# NE555.net
KiCad netlist of a schematic drawn in Altium Designer
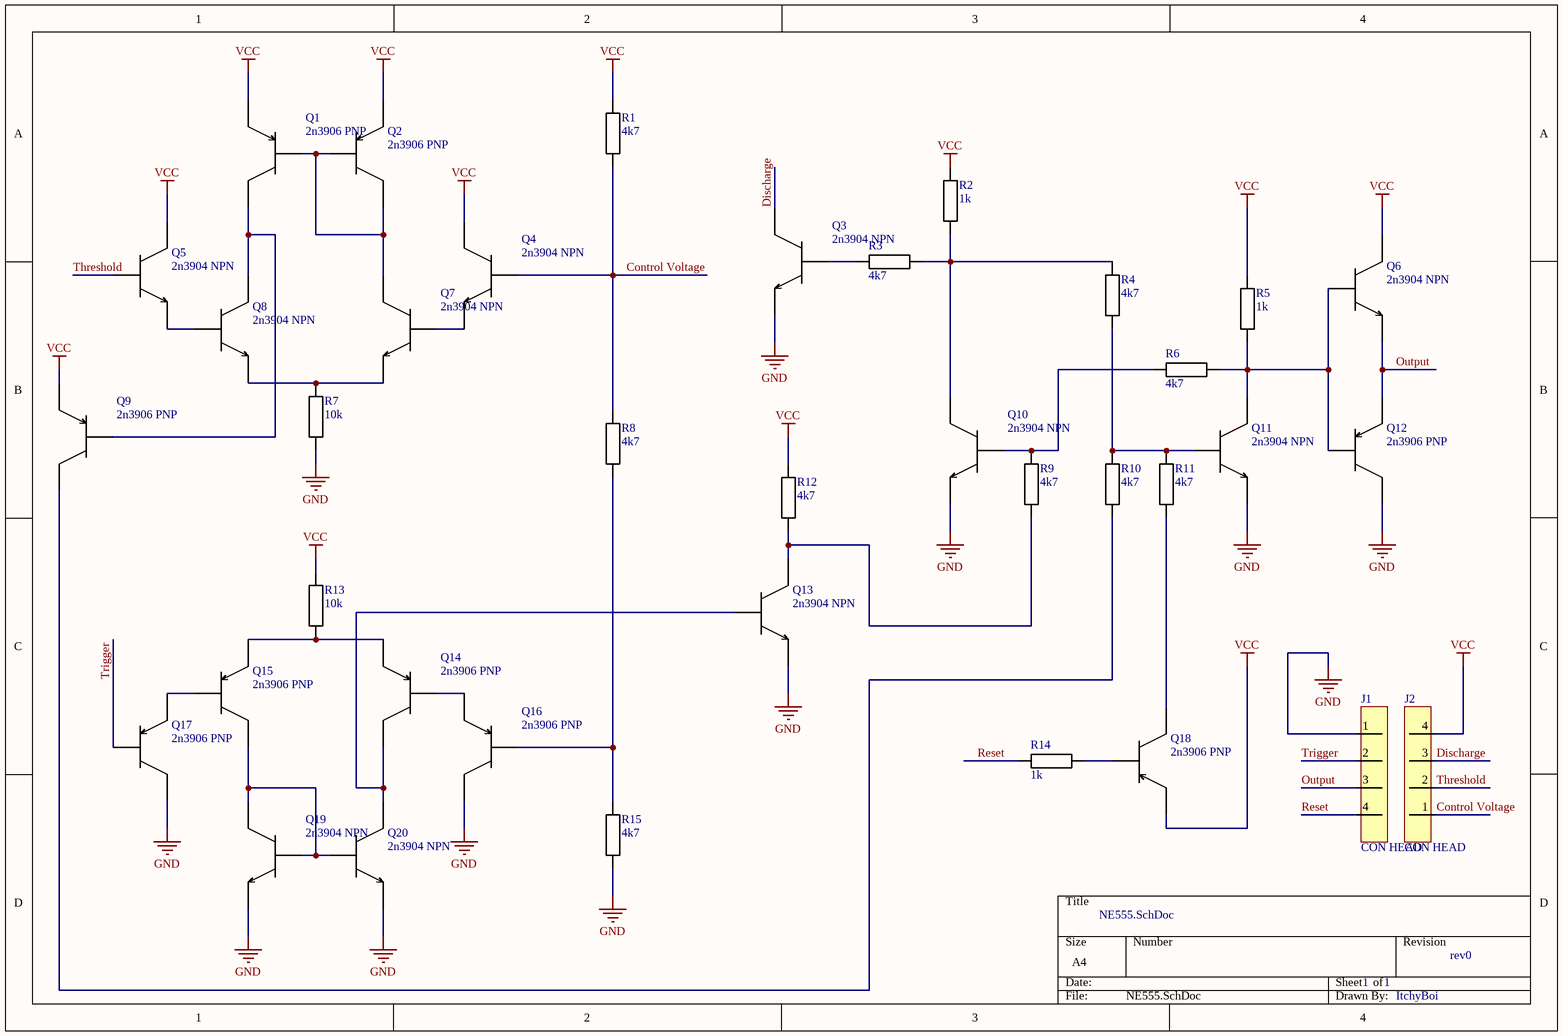
[diagram p0: NE555.SchDoc]

(export (version "E")
  (design (tool "Eeschema 10.0.6"))
  (components
    (comp (ref "J1")
      (value "CON HEAD")
      (footprint "SMT 4 HEADER 2.54")
      (description "CONN HEADER 4POS VERT 2.54MM SMD")
      (fields (field (name "MANUFACTURER") "Molex") (field (name "MANUFACTURER PART NUMBER") "0878980426"))
      (libsource (lib "") (part "0878980426_1"))
    )
    (comp (ref "J2")
      (value "CON HEAD")
      (footprint "SMT 4 HEADER 2.54")
      (description "CONN HEADER 4POS VERT 2.54MM SMD")
      (fields (field (name "MANUFACTURER") "Molex") (field (name "MANUFACTURER PART NUMBER") "0878980426"))
      (libsource (lib "Schlib1") (part "0878980426"))
    )
    (comp (ref "Q1")
      (value "2n3906 PNP")
      (footprint "SOT95P240X110-3N")
      (description "TRANS PNP 40V 0.2A SOT-23")
      (fields
        (field (name "MANUFACTURER") "ON Semiconductor / Fairchild")
        (field (name "MANUFACTURER PART NUMBER") "MMBT3906")
      )
      (libsource (lib "Schlib1") (part "MMBT3906"))
    )
    (comp (ref "Q2")
      (value "2n3906 PNP")
      (footprint "SOT95P240X110-3N")
      (description "TRANS PNP 40V 0.2A SOT-23")
      (fields
        (field (name "MANUFACTURER") "ON Semiconductor / Fairchild")
        (field (name "MANUFACTURER PART NUMBER") "MMBT3906")
      )
      (libsource (lib "Schlib1") (part "MMBT3906"))
    )
    (comp (ref "Q3")
      (value "2n3904 NPN")
      (footprint "SOT95P240X110-3N")
      (description "Trans Gp Bjt NPN 40V 0.2A 3-PIN SOT-23 T/r Trans Gp Bjt NPN 40V 0.2A 3-PIN SOT-23 T/r")
      (fields
        (field (name "MANUFACTURER") "ON Semiconductor / Fairchild")
        (field (name "MANUFACTURER PART NUMBER") "MMBT3904")
      )
      (libsource (lib "Schlib1") (part "MMBT3904"))
    )
    (comp (ref "Q4")
      (value "2n3904 NPN")
      (footprint "SOT95P240X110-3N")
      (description "Trans Gp Bjt NPN 40V 0.2A 3-PIN SOT-23 T/r Trans Gp Bjt NPN 40V 0.2A 3-PIN SOT-23 T/r")
      (fields
        (field (name "MANUFACTURER") "ON Semiconductor / Fairchild")
        (field (name "MANUFACTURER PART NUMBER") "MMBT3904")
      )
      (libsource (lib "Schlib1") (part "MMBT3904"))
    )
    (comp (ref "Q5")
      (value "2n3904 NPN")
      (footprint "SOT95P240X110-3N")
      (description "Trans Gp Bjt NPN 40V 0.2A 3-PIN SOT-23 T/r Trans Gp Bjt NPN 40V 0.2A 3-PIN SOT-23 T/r")
      (fields
        (field (name "MANUFACTURER") "ON Semiconductor / Fairchild")
        (field (name "MANUFACTURER PART NUMBER") "MMBT3904")
      )
      (libsource (lib "Schlib1") (part "MMBT3904"))
    )
    (comp (ref "Q6")
      (value "2n3904 NPN")
      (footprint "SOT95P240X110-3N")
      (description "Trans Gp Bjt NPN 40V 0.2A 3-PIN SOT-23 T/r Trans Gp Bjt NPN 40V 0.2A 3-PIN SOT-23 T/r")
      (fields
        (field (name "MANUFACTURER") "ON Semiconductor / Fairchild")
        (field (name "MANUFACTURER PART NUMBER") "MMBT3904")
      )
      (libsource (lib "Schlib1") (part "MMBT3904"))
    )
    (comp (ref "Q7")
      (value "2n3904 NPN")
      (footprint "SOT95P240X110-3N")
      (description "Trans Gp Bjt NPN 40V 0.2A 3-PIN SOT-23 T/r Trans Gp Bjt NPN 40V 0.2A 3-PIN SOT-23 T/r")
      (fields
        (field (name "MANUFACTURER") "ON Semiconductor / Fairchild")
        (field (name "MANUFACTURER PART NUMBER") "MMBT3904")
      )
      (libsource (lib "Schlib1") (part "MMBT3904"))
    )
    (comp (ref "Q8")
      (value "2n3904 NPN")
      (footprint "SOT95P240X110-3N")
      (description "Trans Gp Bjt NPN 40V 0.2A 3-PIN SOT-23 T/r Trans Gp Bjt NPN 40V 0.2A 3-PIN SOT-23 T/r")
      (fields
        (field (name "MANUFACTURER") "ON Semiconductor / Fairchild")
        (field (name "MANUFACTURER PART NUMBER") "MMBT3904")
      )
      (libsource (lib "Schlib1") (part "MMBT3904"))
    )
    (comp (ref "Q9")
      (value "2n3906 PNP")
      (footprint "SOT95P240X110-3N")
      (description "TRANS PNP 40V 0.2A SOT-23")
      (fields
        (field (name "MANUFACTURER") "ON Semiconductor / Fairchild")
        (field (name "MANUFACTURER PART NUMBER") "MMBT3906")
      )
      (libsource (lib "Schlib1") (part "MMBT3906"))
    )
    (comp (ref "Q10")
      (value "2n3904 NPN")
      (footprint "SOT95P240X110-3N")
      (description "Trans Gp Bjt NPN 40V 0.2A 3-PIN SOT-23 T/r Trans Gp Bjt NPN 40V 0.2A 3-PIN SOT-23 T/r")
      (fields
        (field (name "MANUFACTURER") "ON Semiconductor / Fairchild")
        (field (name "MANUFACTURER PART NUMBER") "MMBT3904")
      )
      (libsource (lib "Schlib1") (part "MMBT3904"))
    )
    (comp (ref "Q11")
      (value "2n3904 NPN")
      (footprint "SOT95P240X110-3N")
      (description "Trans Gp Bjt NPN 40V 0.2A 3-PIN SOT-23 T/r Trans Gp Bjt NPN 40V 0.2A 3-PIN SOT-23 T/r")
      (fields
        (field (name "MANUFACTURER") "ON Semiconductor / Fairchild")
        (field (name "MANUFACTURER PART NUMBER") "MMBT3904")
      )
      (libsource (lib "Schlib1") (part "MMBT3904"))
    )
    (comp (ref "Q12")
      (value "2n3906 PNP")
      (footprint "SOT95P240X110-3N")
      (description "TRANS PNP 40V 0.2A SOT-23")
      (fields
        (field (name "MANUFACTURER") "ON Semiconductor / Fairchild")
        (field (name "MANUFACTURER PART NUMBER") "MMBT3906")
      )
      (libsource (lib "Schlib1") (part "MMBT3906"))
    )
    (comp (ref "Q13")
      (value "2n3904 NPN")
      (footprint "SOT95P240X110-3N")
      (description "Trans Gp Bjt NPN 40V 0.2A 3-PIN SOT-23 T/r Trans Gp Bjt NPN 40V 0.2A 3-PIN SOT-23 T/r")
      (fields
        (field (name "MANUFACTURER") "ON Semiconductor / Fairchild")
        (field (name "MANUFACTURER PART NUMBER") "MMBT3904")
      )
      (libsource (lib "Schlib1") (part "MMBT3904"))
    )
    (comp (ref "Q14")
      (value "2n3906 PNP")
      (footprint "SOT95P240X110-3N")
      (description "TRANS PNP 40V 0.2A SOT-23")
      (fields
        (field (name "MANUFACTURER") "ON Semiconductor / Fairchild")
        (field (name "MANUFACTURER PART NUMBER") "MMBT3906")
      )
      (libsource (lib "Schlib1") (part "MMBT3906"))
    )
    (comp (ref "Q15")
      (value "2n3906 PNP")
      (footprint "SOT95P240X110-3N")
      (description "TRANS PNP 40V 0.2A SOT-23")
      (fields
        (field (name "MANUFACTURER") "ON Semiconductor / Fairchild")
        (field (name "MANUFACTURER PART NUMBER") "MMBT3906")
      )
      (libsource (lib "Schlib1") (part "MMBT3906"))
    )
    (comp (ref "Q16")
      (value "2n3906 PNP")
      (footprint "SOT95P240X110-3N")
      (description "TRANS PNP 40V 0.2A SOT-23")
      (fields
        (field (name "MANUFACTURER") "ON Semiconductor / Fairchild")
        (field (name "MANUFACTURER PART NUMBER") "MMBT3906")
      )
      (libsource (lib "Schlib1") (part "MMBT3906"))
    )
    (comp (ref "Q17")
      (value "2n3906 PNP")
      (footprint "SOT95P240X110-3N")
      (description "TRANS PNP 40V 0.2A SOT-23")
      (fields
        (field (name "MANUFACTURER") "ON Semiconductor / Fairchild")
        (field (name "MANUFACTURER PART NUMBER") "MMBT3906")
      )
      (libsource (lib "Schlib1") (part "MMBT3906"))
    )
    (comp (ref "Q18")
      (value "2n3906 PNP")
      (footprint "SOT95P240X110-3N")
      (description "TRANS PNP 40V 0.2A SOT-23")
      (fields
        (field (name "MANUFACTURER") "ON Semiconductor / Fairchild")
        (field (name "MANUFACTURER PART NUMBER") "MMBT3906")
      )
      (libsource (lib "Schlib1") (part "MMBT3906"))
    )
    (comp (ref "Q19")
      (value "2n3904 NPN")
      (footprint "SOT95P240X110-3N")
      (description "Trans Gp Bjt NPN 40V 0.2A 3-PIN SOT-23 T/r Trans Gp Bjt NPN 40V 0.2A 3-PIN SOT-23 T/r")
      (fields
        (field (name "MANUFACTURER") "ON Semiconductor / Fairchild")
        (field (name "MANUFACTURER PART NUMBER") "MMBT3904")
      )
      (libsource (lib "Schlib1") (part "MMBT3904"))
    )
    (comp (ref "Q20")
      (value "2n3904 NPN")
      (footprint "SOT95P240X110-3N")
      (description "Trans Gp Bjt NPN 40V 0.2A 3-PIN SOT-23 T/r Trans Gp Bjt NPN 40V 0.2A 3-PIN SOT-23 T/r")
      (fields
        (field (name "MANUFACTURER") "ON Semiconductor / Fairchild")
        (field (name "MANUFACTURER PART NUMBER") "MMBT3904")
      )
      (libsource (lib "Schlib1") (part "MMBT3904"))
    )
    (comp (ref "R1")
      (value "4k7")
      (footprint "R0805")
      (fields
        (field (name "MANUFACTURER") "Vishay")
        (field (name "MANUFACTURER PART NUMBER") "CRCW08054K70FKEA")
        (field (name "TOLERANCE") "1%")
      )
      (libsource (lib "Schlib1") (part "CRCW08054K70FKEA"))
    )
    (comp (ref "R2")
      (value "1k")
      (footprint "R0805")
      (description "Res Thick Film 0805 1K Ohm 1% 0.125W(1/8W) ±100ppm/C Pad SMD Automotive T/R")
      (fields
        (field (name "MANUFACTURER") "Vishay Dale")
        (field (name "MANUFACTURER PART NUMBER") "CRCW08051K00FKEA")
      )
      (libsource (lib "Schlib1") (part "CRCW08051K00FKEA"))
    )
    (comp (ref "R3")
      (value "4k7")
      (footprint "R0805")
      (fields
        (field (name "MANUFACTURER") "Vishay")
        (field (name "MANUFACTURER PART NUMBER") "CRCW08054K70FKEA")
        (field (name "TOLERANCE") "1%")
      )
      (libsource (lib "Schlib1") (part "CRCW08054K70FKEA"))
    )
    (comp (ref "R4")
      (value "4k7")
      (footprint "R0805")
      (fields
        (field (name "MANUFACTURER") "Vishay")
        (field (name "MANUFACTURER PART NUMBER") "CRCW08054K70FKEA")
        (field (name "TOLERANCE") "1%")
      )
      (libsource (lib "Schlib1") (part "CRCW08054K70FKEA"))
    )
    (comp (ref "R5")
      (value "1k")
      (footprint "R0805")
      (description "Res Thick Film 0805 1K Ohm 1% 0.125W(1/8W) ±100ppm/C Pad SMD Automotive T/R")
      (fields
        (field (name "MANUFACTURER") "Vishay Dale")
        (field (name "MANUFACTURER PART NUMBER") "CRCW08051K00FKEA")
      )
      (libsource (lib "Schlib1") (part "CRCW08051K00FKEA"))
    )
    (comp (ref "R6")
      (value "4k7")
      (footprint "R0805")
      (fields
        (field (name "MANUFACTURER") "Vishay")
        (field (name "MANUFACTURER PART NUMBER") "CRCW08054K70FKEA")
        (field (name "TOLERANCE") "1%")
      )
      (libsource (lib "Schlib1") (part "CRCW08054K70FKEA"))
    )
    (comp (ref "R7")
      (value "10k")
      (footprint "R0805")
      (fields
        (field (name "MANUFACTURER") "Vishay")
        (field (name "MANUFACTURER PART NUMBER") "CRCW080510K0FKEA")
        (field (name "TOLERANCE") "1%")
      )
      (libsource (lib "Schlib1") (part "CRCW080510K0FKEA"))
    )
    (comp (ref "R8")
      (value "4k7")
      (footprint "R0805")
      (fields
        (field (name "MANUFACTURER") "Vishay")
        (field (name "MANUFACTURER PART NUMBER") "CRCW08054K70FKEA")
        (field (name "TOLERANCE") "1%")
      )
      (libsource (lib "Schlib1") (part "CRCW08054K70FKEA"))
    )
    (comp (ref "R9")
      (value "4k7")
      (footprint "R0805")
      (fields
        (field (name "MANUFACTURER") "Vishay")
        (field (name "MANUFACTURER PART NUMBER") "CRCW08054K70FKEA")
        (field (name "TOLERANCE") "1%")
      )
      (libsource (lib "Schlib1") (part "CRCW08054K70FKEA"))
    )
    (comp (ref "R10")
      (value "4k7")
      (footprint "R0805")
      (fields
        (field (name "MANUFACTURER") "Vishay")
        (field (name "MANUFACTURER PART NUMBER") "CRCW08054K70FKEA")
        (field (name "TOLERANCE") "1%")
      )
      (libsource (lib "Schlib1") (part "CRCW08054K70FKEA"))
    )
    (comp (ref "R11")
      (value "4k7")
      (footprint "R0805")
      (fields
        (field (name "MANUFACTURER") "Vishay")
        (field (name "MANUFACTURER PART NUMBER") "CRCW08054K70FKEA")
        (field (name "TOLERANCE") "1%")
      )
      (libsource (lib "Schlib1") (part "CRCW08054K70FKEA"))
    )
    (comp (ref "R12")
      (value "4k7")
      (footprint "R0805")
      (fields
        (field (name "MANUFACTURER") "Vishay")
        (field (name "MANUFACTURER PART NUMBER") "CRCW08054K70FKEA")
        (field (name "TOLERANCE") "1%")
      )
      (libsource (lib "Schlib1") (part "CRCW08054K70FKEA"))
    )
    (comp (ref "R13")
      (value "10k")
      (footprint "R0805")
      (fields
        (field (name "MANUFACTURER") "Vishay")
        (field (name "MANUFACTURER PART NUMBER") "CRCW080510K0FKEA")
        (field (name "TOLERANCE") "1%")
      )
      (libsource (lib "Schlib1") (part "CRCW080510K0FKEA"))
    )
    (comp (ref "R14")
      (value "1k")
      (footprint "R0805")
      (description "Res Thick Film 0805 1K Ohm 1% 0.125W(1/8W) ±100ppm/C Pad SMD Automotive T/R")
      (fields
        (field (name "MANUFACTURER") "Vishay Dale")
        (field (name "MANUFACTURER PART NUMBER") "CRCW08051K00FKEA")
      )
      (libsource (lib "Schlib1") (part "CRCW08051K00FKEA"))
    )
    (comp (ref "R15")
      (value "4k7")
      (footprint "R0805")
      (fields
        (field (name "MANUFACTURER") "Vishay")
        (field (name "MANUFACTURER PART NUMBER") "CRCW08054K70FKEA")
        (field (name "TOLERANCE") "1%")
      )
      (libsource (lib "Schlib1") (part "CRCW08054K70FKEA"))
    )
  )
  (nets
    (net (code "1") (name "/Control Voltage") (class "Default")
      (node (ref "J2") (pin "1") (pinfunction "1_1") (pintype "passive"))
      (node (ref "Q4") (pin "1") (pinfunction "B_1") (pintype "passive"))
      (node (ref "R1") (pin "2") (pinfunction "2_2") (pintype "passive"))
      (node (ref "R8") (pin "1") (pinfunction "1_1") (pintype "passive"))
    )
    (net (code "2") (name "/Discharge") (class "Default")
      (node (ref "J2") (pin "3") (pinfunction "3_3") (pintype "passive"))
      (node (ref "Q3") (pin "3") (pinfunction "C_3") (pintype "open_collector"))
    )
    (net (code "3") (name "/Output") (class "Default")
      (node (ref "J1") (pin "3") (pinfunction "3_3") (pintype "passive"))
      (node (ref "Q12") (pin "2") (pinfunction "E_2") (pintype "open_emitter"))
      (node (ref "Q6") (pin "2") (pinfunction "E_2") (pintype "open_emitter"))
    )
    (net (code "4") (name "/Reset") (class "Default")
      (node (ref "J1") (pin "4") (pinfunction "4_4") (pintype "passive"))
      (node (ref "R14") (pin "2") (pinfunction "2_2") (pintype "passive"))
    )
    (net (code "5") (name "/Threshold") (class "Default")
      (node (ref "J2") (pin "2") (pinfunction "2_2") (pintype "passive"))
      (node (ref "Q5") (pin "1") (pinfunction "B_1") (pintype "passive"))
    )
    (net (code "6") (name "/Trigger") (class "Default")
      (node (ref "J1") (pin "2") (pinfunction "2_2") (pintype "passive"))
      (node (ref "Q17") (pin "1") (pinfunction "B_1") (pintype "passive"))
    )
    (net (code "7") (name "GND") (class "Default")
      (node (ref "J1") (pin "1") (pinfunction "1_1") (pintype "passive"))
      (node (ref "Q10") (pin "2") (pinfunction "E_2") (pintype "open_emitter"))
      (node (ref "Q11") (pin "2") (pinfunction "E_2") (pintype "open_emitter"))
      (node (ref "Q12") (pin "3") (pinfunction "C_3") (pintype "open_collector"))
      (node (ref "Q13") (pin "2") (pinfunction "E_2") (pintype "open_emitter"))
      (node (ref "Q16") (pin "3") (pinfunction "C_3") (pintype "open_collector"))
      (node (ref "Q17") (pin "3") (pinfunction "C_3") (pintype "open_collector"))
      (node (ref "Q19") (pin "2") (pinfunction "E_2") (pintype "open_emitter"))
      (node (ref "Q20") (pin "2") (pinfunction "E_2") (pintype "open_emitter"))
      (node (ref "Q3") (pin "2") (pinfunction "E_2") (pintype "open_emitter"))
      (node (ref "R15") (pin "2") (pinfunction "2_2") (pintype "passive"))
      (node (ref "R7") (pin "1") (pinfunction "1_1") (pintype "passive"))
    )
    (net (code "8") (name "Net-(Q1-B)") (class "Default")
      (node (ref "Q1") (pin "1") (pinfunction "B_1") (pintype "passive"))
      (node (ref "Q2") (pin "1") (pinfunction "B_1") (pintype "passive"))
      (node (ref "Q2") (pin "3") (pinfunction "C_3") (pintype "open_collector"))
      (node (ref "Q7") (pin "3") (pinfunction "C_3") (pintype "open_collector"))
    )
    (net (code "9") (name "Net-(Q1-C)") (class "Default")
      (node (ref "Q1") (pin "3") (pinfunction "C_3") (pintype "open_collector"))
      (node (ref "Q8") (pin "3") (pinfunction "C_3") (pintype "open_collector"))
      (node (ref "Q9") (pin "1") (pinfunction "B_1") (pintype "passive"))
    )
    (net (code "10") (name "Net-(Q3-B)") (class "Default")
      (node (ref "Q3") (pin "1") (pinfunction "B_1") (pintype "passive"))
      (node (ref "R3") (pin "2") (pinfunction "2_2") (pintype "passive"))
    )
    (net (code "11") (name "Net-(Q4-E)") (class "Default")
      (node (ref "Q4") (pin "2") (pinfunction "E_2") (pintype "open_emitter"))
      (node (ref "Q7") (pin "1") (pinfunction "B_1") (pintype "passive"))
    )
    (net (code "12") (name "Net-(Q5-E)") (class "Default")
      (node (ref "Q5") (pin "2") (pinfunction "E_2") (pintype "open_emitter"))
      (node (ref "Q8") (pin "1") (pinfunction "B_1") (pintype "passive"))
    )
    (net (code "13") (name "Net-(Q7-E)") (class "Default")
      (node (ref "Q7") (pin "2") (pinfunction "E_2") (pintype "open_emitter"))
      (node (ref "Q8") (pin "2") (pinfunction "E_2") (pintype "open_emitter"))
      (node (ref "R7") (pin "2") (pinfunction "2_2") (pintype "passive"))
    )
    (net (code "14") (name "Net-(Q9-C)") (class "Default")
      (node (ref "Q9") (pin "3") (pinfunction "C_3") (pintype "open_collector"))
      (node (ref "R10") (pin "1") (pinfunction "1_1") (pintype "passive"))
    )
    (net (code "15") (name "Net-(Q10-B)") (class "Default")
      (node (ref "Q10") (pin "1") (pinfunction "B_1") (pintype "passive"))
      (node (ref "R6") (pin "1") (pinfunction "1_1") (pintype "passive"))
      (node (ref "R9") (pin "2") (pinfunction "2_2") (pintype "passive"))
    )
    (net (code "16") (name "Net-(Q10-C)") (class "Default")
      (node (ref "Q10") (pin "3") (pinfunction "C_3") (pintype "open_collector"))
      (node (ref "R2") (pin "1") (pinfunction "1_1") (pintype "passive"))
      (node (ref "R3") (pin "1") (pinfunction "1_1") (pintype "passive"))
      (node (ref "R4") (pin "2") (pinfunction "2_2") (pintype "passive"))
    )
    (net (code "17") (name "Net-(Q11-B)") (class "Default")
      (node (ref "Q11") (pin "1") (pinfunction "B_1") (pintype "passive"))
      (node (ref "R10") (pin "2") (pinfunction "2_2") (pintype "passive"))
      (node (ref "R11") (pin "1") (pinfunction "1_1") (pintype "passive"))
      (node (ref "R4") (pin "1") (pinfunction "1_1") (pintype "passive"))
    )
    (net (code "18") (name "Net-(Q11-C)") (class "Default")
      (node (ref "Q11") (pin "3") (pinfunction "C_3") (pintype "open_collector"))
      (node (ref "Q12") (pin "1") (pinfunction "B_1") (pintype "passive"))
      (node (ref "Q6") (pin "1") (pinfunction "B_1") (pintype "passive"))
      (node (ref "R5") (pin "1") (pinfunction "1_1") (pintype "passive"))
      (node (ref "R6") (pin "2") (pinfunction "2_2") (pintype "passive"))
    )
    (net (code "19") (name "Net-(Q13-B)") (class "Default")
      (node (ref "Q13") (pin "1") (pinfunction "B_1") (pintype "passive"))
      (node (ref "Q14") (pin "3") (pinfunction "C_3") (pintype "open_collector"))
      (node (ref "Q20") (pin "3") (pinfunction "C_3") (pintype "open_collector"))
    )
    (net (code "20") (name "Net-(Q13-C)") (class "Default")
      (node (ref "Q13") (pin "3") (pinfunction "C_3") (pintype "open_collector"))
      (node (ref "R12") (pin "2") (pinfunction "2_2") (pintype "passive"))
      (node (ref "R9") (pin "1") (pinfunction "1_1") (pintype "passive"))
    )
    (net (code "21") (name "Net-(Q14-B)") (class "Default")
      (node (ref "Q14") (pin "1") (pinfunction "B_1") (pintype "passive"))
      (node (ref "Q16") (pin "2") (pinfunction "E_2") (pintype "open_emitter"))
    )
    (net (code "22") (name "Net-(Q14-E)") (class "Default")
      (node (ref "Q14") (pin "2") (pinfunction "E_2") (pintype "open_emitter"))
      (node (ref "Q15") (pin "2") (pinfunction "E_2") (pintype "open_emitter"))
      (node (ref "R13") (pin "1") (pinfunction "1_1") (pintype "passive"))
    )
    (net (code "23") (name "Net-(Q15-B)") (class "Default")
      (node (ref "Q15") (pin "1") (pinfunction "B_1") (pintype "passive"))
      (node (ref "Q17") (pin "2") (pinfunction "E_2") (pintype "open_emitter"))
    )
    (net (code "24") (name "Net-(Q15-C)") (class "Default")
      (node (ref "Q15") (pin "3") (pinfunction "C_3") (pintype "open_collector"))
      (node (ref "Q19") (pin "1") (pinfunction "B_1") (pintype "passive"))
      (node (ref "Q19") (pin "3") (pinfunction "C_3") (pintype "open_collector"))
      (node (ref "Q20") (pin "1") (pinfunction "B_1") (pintype "passive"))
    )
    (net (code "25") (name "Net-(Q16-B)") (class "Default")
      (node (ref "Q16") (pin "1") (pinfunction "B_1") (pintype "passive"))
      (node (ref "R15") (pin "1") (pinfunction "1_1") (pintype "passive"))
      (node (ref "R8") (pin "2") (pinfunction "2_2") (pintype "passive"))
    )
    (net (code "26") (name "Net-(Q18-B)") (class "Default")
      (node (ref "Q18") (pin "1") (pinfunction "B_1") (pintype "passive"))
      (node (ref "R14") (pin "1") (pinfunction "1_1") (pintype "passive"))
    )
    (net (code "27") (name "Net-(Q18-C)") (class "Default")
      (node (ref "Q18") (pin "3") (pinfunction "C_3") (pintype "open_collector"))
      (node (ref "R11") (pin "2") (pinfunction "2_2") (pintype "passive"))
    )
    (net (code "28") (name "VCC") (class "Default")
      (node (ref "J2") (pin "4") (pinfunction "4_4") (pintype "passive"))
      (node (ref "Q1") (pin "2") (pinfunction "E_2") (pintype "open_emitter"))
      (node (ref "Q18") (pin "2") (pinfunction "E_2") (pintype "open_emitter"))
      (node (ref "Q2") (pin "2") (pinfunction "E_2") (pintype "open_emitter"))
      (node (ref "Q4") (pin "3") (pinfunction "C_3") (pintype "open_collector"))
      (node (ref "Q5") (pin "3") (pinfunction "C_3") (pintype "open_collector"))
      (node (ref "Q6") (pin "3") (pinfunction "C_3") (pintype "open_collector"))
      (node (ref "Q9") (pin "2") (pinfunction "E_2") (pintype "open_emitter"))
      (node (ref "R1") (pin "1") (pinfunction "1_1") (pintype "passive"))
      (node (ref "R12") (pin "1") (pinfunction "1_1") (pintype "passive"))
      (node (ref "R13") (pin "2") (pinfunction "2_2") (pintype "passive"))
      (node (ref "R2") (pin "2") (pinfunction "2_2") (pintype "passive"))
      (node (ref "R5") (pin "2") (pinfunction "2_2") (pintype "passive"))
    )
  )
)
